# head.net
KiCad netlist of a schematic drawn in EAGLE
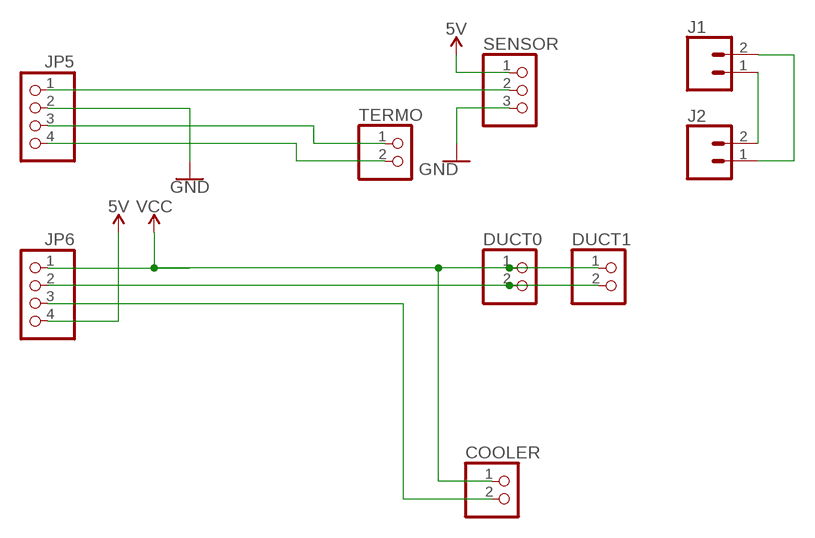
[diagram p0: schematic, sheet 1]

(export (version "E")
  (design (tool "Eeschema 10.0.6"))
  (components
    (comp (ref "COOLER")
      (value "PINHD-1X2")
      (footprint "eagle-import:1X02")
      (libsource (lib "eagle-import") (part "PINHD-1X2"))
    )
    (comp (ref "DUCT0")
      (value "PINHD-1X2")
      (footprint "eagle-import:1X02")
      (libsource (lib "eagle-import") (part "PINHD-1X2"))
    )
    (comp (ref "DUCT1")
      (value "PINHD-1X2")
      (footprint "eagle-import:1X02")
      (libsource (lib "eagle-import") (part "PINHD-1X2"))
    )
    (comp (ref "J1")
      (value "CONN_025MM")
      (footprint "eagle-import:SCREWTERMINAL-5MM-2")
      (libsource (lib "eagle-import") (part "CONN_025MM"))
    )
    (comp (ref "J2")
      (value "CONN_025MM")
      (footprint "eagle-import:SCREWTERMINAL-5MM-2")
      (libsource (lib "eagle-import") (part "CONN_025MM"))
    )
    (comp (ref "JP5")
      (value "PINHD-1X4")
      (footprint "eagle-import:1X04")
      (libsource (lib "eagle-import") (part "PINHD-1X4"))
    )
    (comp (ref "JP6")
      (value "PINHD-1X4")
      (footprint "eagle-import:1X04")
      (libsource (lib "eagle-import") (part "PINHD-1X4"))
    )
    (comp (ref "SENSOR")
      (value "PINHD-1X3")
      (footprint "eagle-import:1X03")
      (libsource (lib "eagle-import") (part "PINHD-1X3"))
    )
    (comp (ref "TERMO")
      (value "PINHD-1X2")
      (footprint "eagle-import:1X02")
      (libsource (lib "eagle-import") (part "PINHD-1X2"))
    )
  )
  (nets
    (net (code "1") (name "5V") (class "Default")
      (node (ref "JP6") (pin "4") (pinfunction "4_4") (pintype "passive"))
      (node (ref "SENSOR") (pin "1") (pinfunction "1_1") (pintype "passive"))
    )
    (net (code "2") (name "GND") (class "Default")
      (node (ref "JP5") (pin "2") (pinfunction "2_2") (pintype "passive"))
      (node (ref "SENSOR") (pin "3") (pinfunction "3_3") (pintype "passive"))
    )
    (net (code "3") (name "Net-(COOLER-Pad2)") (class "Default")
      (node (ref "COOLER") (pin "2") (pinfunction "2_2") (pintype "passive"))
      (node (ref "JP6") (pin "3") (pinfunction "3_3") (pintype "passive"))
    )
    (net (code "4") (name "Net-(DUCT0-Pad2)") (class "Default")
      (node (ref "DUCT0") (pin "2") (pinfunction "2_2") (pintype "passive"))
      (node (ref "DUCT1") (pin "2") (pinfunction "2_2") (pintype "passive"))
      (node (ref "JP6") (pin "2") (pinfunction "2_2") (pintype "passive"))
    )
    (net (code "5") (name "Net-(J1-Pad1)") (class "Default")
      (node (ref "J1") (pin "1") (pinfunction "1_1") (pintype "passive"))
      (node (ref "J2") (pin "2") (pinfunction "2_2") (pintype "passive"))
    )
    (net (code "6") (name "Net-(J1-Pad2)") (class "Default")
      (node (ref "J1") (pin "2") (pinfunction "2_2") (pintype "passive"))
      (node (ref "J2") (pin "1") (pinfunction "1_1") (pintype "passive"))
    )
    (net (code "7") (name "Net-(JP5-Pad1)") (class "Default")
      (node (ref "JP5") (pin "1") (pinfunction "1_1") (pintype "passive"))
      (node (ref "SENSOR") (pin "2") (pinfunction "2_2") (pintype "passive"))
    )
    (net (code "8") (name "Net-(JP5-Pad3)") (class "Default")
      (node (ref "JP5") (pin "3") (pinfunction "3_3") (pintype "passive"))
      (node (ref "TERMO") (pin "1") (pinfunction "1_1") (pintype "passive"))
    )
    (net (code "9") (name "Net-(JP5-Pad4)") (class "Default")
      (node (ref "JP5") (pin "4") (pinfunction "4_4") (pintype "passive"))
      (node (ref "TERMO") (pin "2") (pinfunction "2_2") (pintype "passive"))
    )
    (net (code "10") (name "VCC") (class "Default")
      (node (ref "COOLER") (pin "1") (pinfunction "1_1") (pintype "passive"))
      (node (ref "DUCT0") (pin "1") (pinfunction "1_1") (pintype "passive"))
      (node (ref "DUCT1") (pin "1") (pinfunction "1_1") (pintype "passive"))
      (node (ref "JP6") (pin "1") (pinfunction "1_1") (pintype "passive"))
    )
  )
)
